# Connectors.net
KiCad netlist of a schematic drawn in Altium Designer
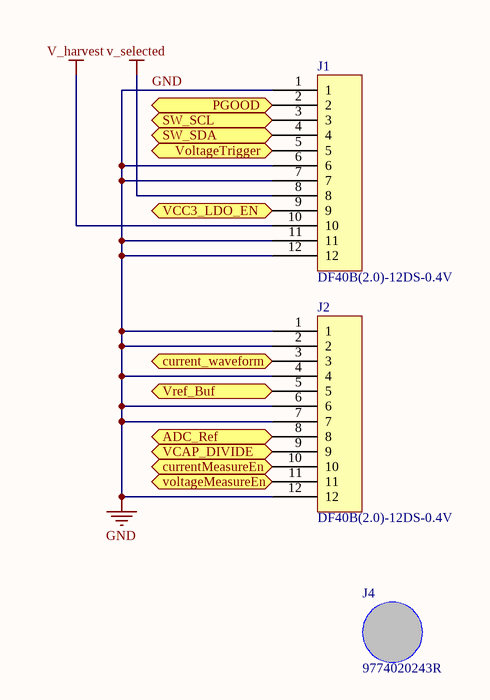
[diagram p0: Connectors.SchDoc]

(export (version "E")
  (design (tool "Eeschema 10.0.6"))
  (components
    (comp (ref "J1")
      (value "DF40B(2.0)-12DS-0.4V")
      (footprint "DF40B(2.0)-12DS-0.4V")
      (description "Hirose BM20 Series, 0.4mm pitch, 2mm stack height, 12 pos, header")
      (libsource (lib "connectors") (part "DF40B(2.0)-12DS-0.4V"))
    )
    (comp (ref "J2")
      (value "DF40B(2.0)-12DS-0.4V")
      (footprint "DF40B(2.0)-12DS-0.4V")
      (description "Hirose BM20 Series, 0.4mm pitch, 2mm stack height, 12 pos, header")
      (libsource (lib "connectors") (part "DF40B(2.0)-12DS-0.4V"))
    )
    (comp (ref "J4")
      (value "9774020243R")
      (footprint "9774020243R")
      (description "2 mm stack height, m2 standoff")
      (libsource (lib "connectors") (part "9774020243R"))
    )
  )
  (nets
    (net (code "1") (name "/ADC_Ref") (class "Default")
      (node (ref "J2") (pin "8") (pinfunction "8_8") (pintype "passive"))
    )
    (net (code "2") (name "/PGOOD") (class "Default")
      (node (ref "J1") (pin "2") (pinfunction "2_2") (pintype "passive"))
    )
    (net (code "3") (name "/SW_SCL") (class "Default")
      (node (ref "J1") (pin "3") (pinfunction "3_3") (pintype "passive"))
    )
    (net (code "4") (name "/SW_SDA") (class "Default")
      (node (ref "J1") (pin "4") (pinfunction "4_4") (pintype "passive"))
    )
    (net (code "5") (name "/VCAP_DIVIDE") (class "Default")
      (node (ref "J2") (pin "9") (pinfunction "9_9") (pintype "passive"))
    )
    (net (code "6") (name "/VCC3_LDO_EN") (class "Default")
      (node (ref "J1") (pin "9") (pinfunction "9_9") (pintype "passive"))
    )
    (net (code "7") (name "/VoltageTrigger") (class "Default")
      (node (ref "J1") (pin "5") (pinfunction "5_5") (pintype "passive"))
    )
    (net (code "8") (name "/Vref_Buf") (class "Default")
      (node (ref "J2") (pin "5") (pinfunction "5_5") (pintype "passive"))
    )
    (net (code "9") (name "/currentMeasureEn") (class "Default")
      (node (ref "J2") (pin "10") (pinfunction "10_10") (pintype "passive"))
    )
    (net (code "10") (name "/current_waveform") (class "Default")
      (node (ref "J2") (pin "3") (pinfunction "3_3") (pintype "passive"))
    )
    (net (code "11") (name "/voltageMeasureEn") (class "Default")
      (node (ref "J2") (pin "11") (pinfunction "11_11") (pintype "passive"))
    )
    (net (code "12") (name "GND") (class "Default")
      (node (ref "J1") (pin "1") (pinfunction "1_1") (pintype "passive"))
      (node (ref "J1") (pin "11") (pinfunction "11_11") (pintype "passive"))
      (node (ref "J1") (pin "12") (pinfunction "12_12") (pintype "passive"))
      (node (ref "J1") (pin "6") (pinfunction "6_6") (pintype "passive"))
      (node (ref "J1") (pin "7") (pinfunction "7_7") (pintype "passive"))
      (node (ref "J2") (pin "1") (pinfunction "1_1") (pintype "passive"))
      (node (ref "J2") (pin "12") (pinfunction "12_12") (pintype "passive"))
      (node (ref "J2") (pin "2") (pinfunction "2_2") (pintype "passive"))
      (node (ref "J2") (pin "4") (pinfunction "4_4") (pintype "passive"))
      (node (ref "J2") (pin "6") (pinfunction "6_6") (pintype "passive"))
      (node (ref "J2") (pin "7") (pinfunction "7_7") (pintype "passive"))
    )
    (net (code "13") (name "V_harvest") (class "Default")
      (node (ref "J1") (pin "10") (pinfunction "10_10") (pintype "passive"))
    )
    (net (code "14") (name "v_selected") (class "Default")
      (node (ref "J1") (pin "8") (pinfunction "8_8") (pintype "passive"))
    )
  )
)
